# H2BR10.net
KiCad netlist of a schematic drawn in EAGLE
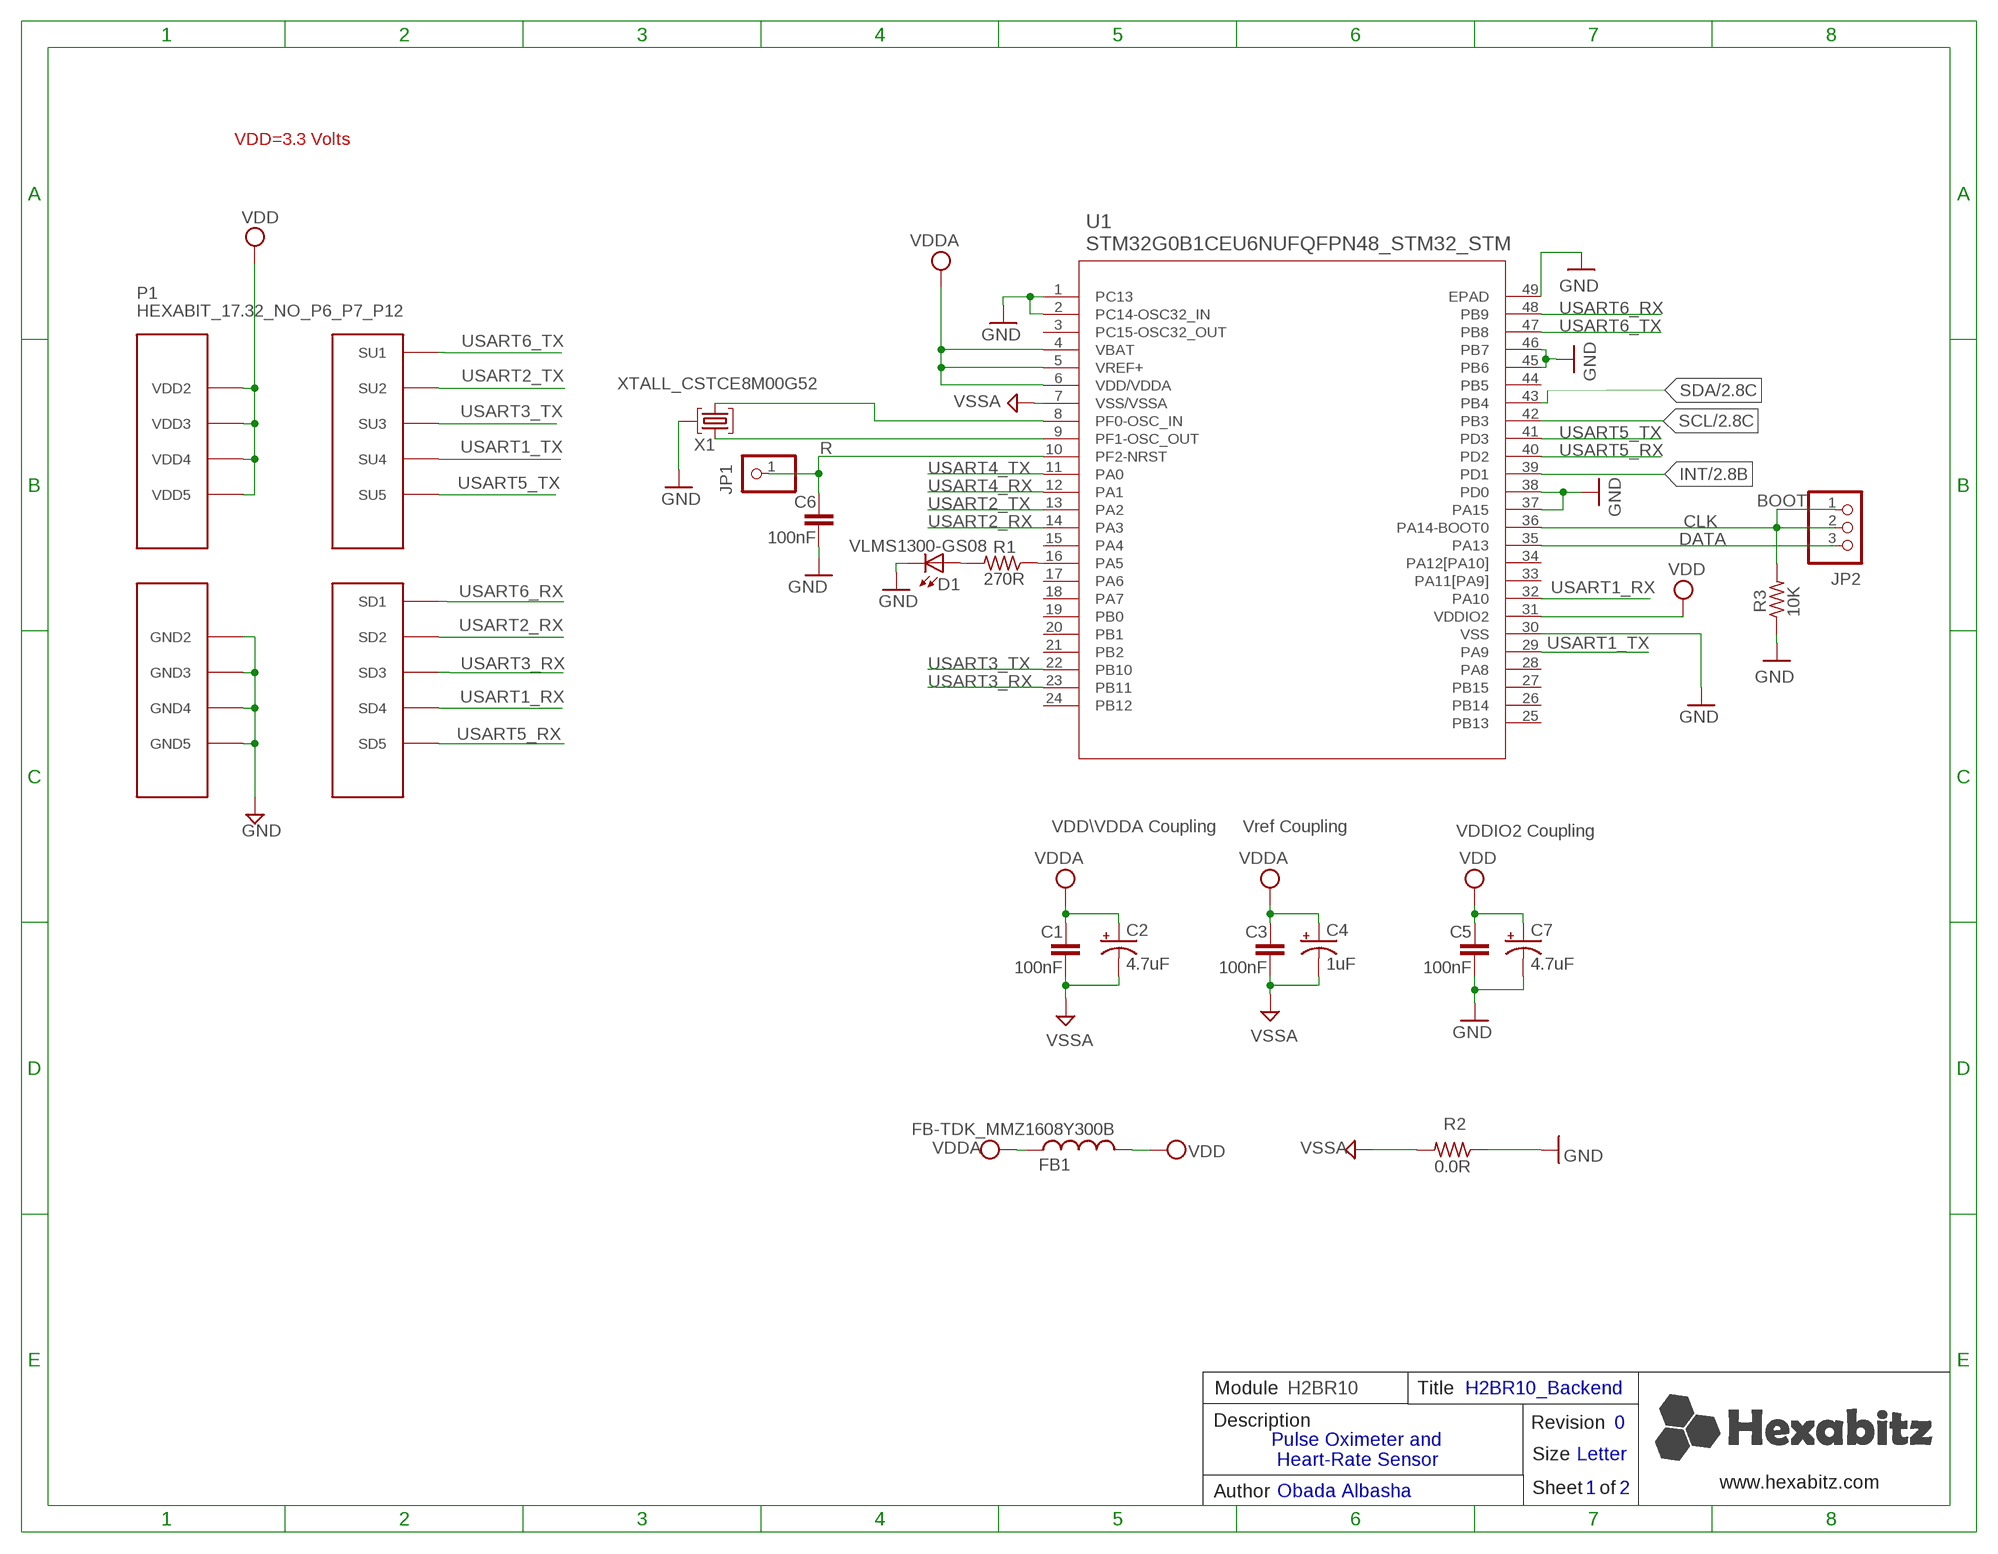
[diagram p0: schematic, sheet 1]
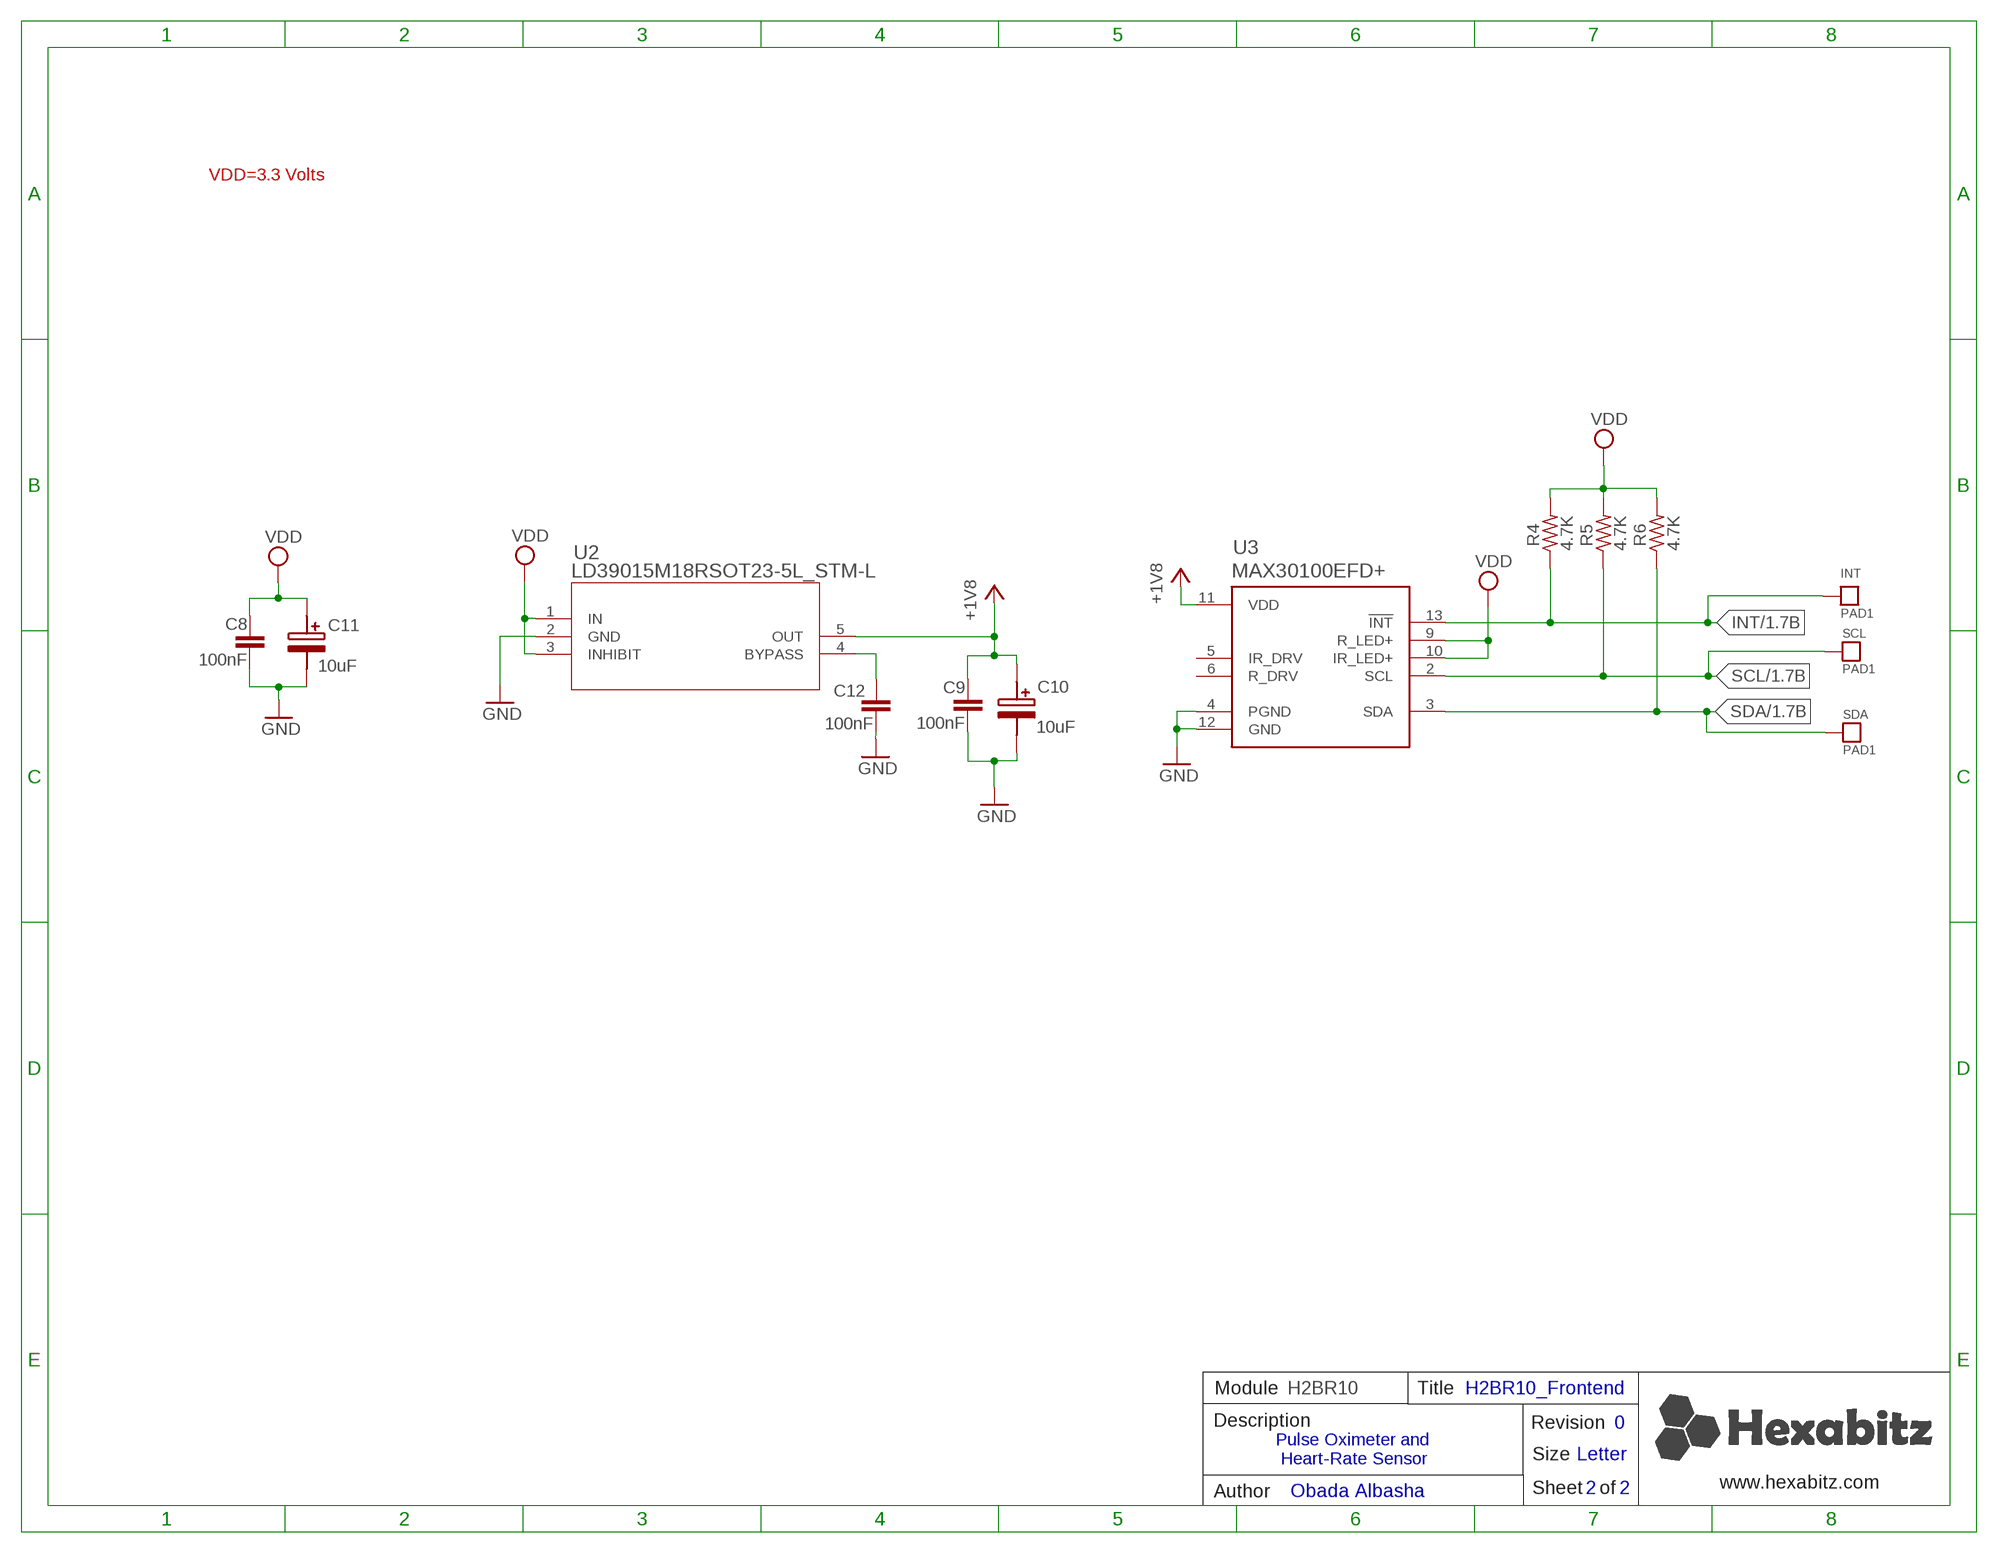
[diagram p1: schematic, sheet 2]

(export (version "E")
  (design (tool "Eeschema 10.0.6"))
  (components
    (comp (ref "C1")
      (value "100nF")
      (footprint "eagle-import:C-0603")
      (libsource (lib "eagle-import") (part "C-0603"))
    )
    (comp (ref "C2")
      (value "4.7uF")
      (footprint "eagle-import:C-0805-POL")
      (libsource (lib "eagle-import") (part "C-0805-POL"))
    )
    (comp (ref "C3")
      (value "100nF")
      (footprint "eagle-import:C-0603")
      (libsource (lib "eagle-import") (part "C-0603"))
    )
    (comp (ref "C4")
      (value "1uF")
      (footprint "eagle-import:C-0805-POL")
      (libsource (lib "eagle-import") (part "C-0805-POL"))
    )
    (comp (ref "C5")
      (value "100nF")
      (footprint "eagle-import:C-0603")
      (libsource (lib "eagle-import") (part "C-0603"))
    )
    (comp (ref "C6")
      (value "100nF")
      (footprint "eagle-import:C-0603")
      (libsource (lib "eagle-import") (part "C-0603"))
    )
    (comp (ref "C7")
      (value "4.7uF")
      (footprint "eagle-import:C-0805-POL")
      (libsource (lib "eagle-import") (part "C-0805-POL"))
    )
    (comp (ref "D1")
      (value "VLMS1300-GS08")
      (footprint "eagle-import:VLMS1300-GS08")
      (fields
        (field (name "MFN") "Vishay")
        (field (name "MPN") "VLMS1300-GS08")
        (field (name "OCTOPART_URL") "https://octopart.com/vlms1300-gs08-vishay-21709201?r=sp&s=_gcP4_q8T1SC6PJQPTQ9yA")
      )
      (libsource (lib "eagle-import") (part "VLMS1300-GS08"))
    )
    (comp (ref "FB1")
      (value "FB-TDK_MMZ1608Y300B")
      (footprint "eagle-import:FB-TDK_MMZ1608Y300B")
      (fields
        (field (name "MFN") "TDK ")
        (field (name "MPN") "MMZ1608Y300B")
        (field (name "OCTOPART_URL") "https://octopart.com/mmz1608y300b-tdk-368280?r=sp&s=cd9_2ZEqQ9q9UNBuQgHAiA")
      )
      (libsource (lib "eagle-import") (part "FB-TDK_MMZ1608Y300B"))
    )
    (comp (ref "JP1")
      (value "R")
      (footprint "eagle-import:1X01")
      (fields (field (name "MPN") "87227-1"))
      (libsource (lib "eagle-import") (part "PINHD-1X1"))
    )
    (comp (ref "JP2")
      (value "PINHD-1X3")
      (footprint "eagle-import:1X03")
      (libsource (lib "eagle-import") (part "PINHD-1X3"))
    )
    (comp (ref "P1")
      (value "HEXABIT_17.32_NO_P6_P7_P12")
      (footprint "eagle-import:HEXABIT_17.32_NO_P6_P7_P12")
      (libsource (lib "eagle-import") (part "HEXABIT_?_NO_P6_P7_P1217.32"))
    )
    (comp (ref "R1")
      (value "270R")
      (footprint "eagle-import:R-0603")
      (libsource (lib "eagle-import") (part "R-0603"))
    )
    (comp (ref "R2")
      (value "0.0R")
      (footprint "eagle-import:R-0603")
      (fields
        (field (name "MFN") "Yageo")
        (field (name "MPN") "RC0603JR-070RL")
        (field (name "OCTOPART_URL") "https://octopart.com/rc0603jr-070rl-yageo-1241539?r=sp&s=X2NteqRjRNWrnx42Y0aliA")
        (field (name "RESISTANCE") "0.0 Ohm")
      )
      (libsource (lib "eagle-import") (part "HEXABITZ_RCLS_33906182_R-0603"))
    )
    (comp (ref "R3")
      (value "10K")
      (footprint "eagle-import:R-0603")
      (libsource (lib "eagle-import") (part "R-0603"))
    )
    (comp (ref "U1")
      (value "STM32G0B1CEU6NUFQFPN48_STM32_STM")
      (footprint "eagle-import:UFQFPN48_STM32_STM")
      (fields
        (field (name "MPN") "STM32G0B1CEU6N")
        (field (name "COPYRIGHT") "Copyright (C) 2022 Ultra Librarian. All rights reserved.")
      )
      (libsource (lib "eagle-import") (part "STM32G0B1CEU6NUFQFPN48_STM32_STM"))
    )
    (comp (ref "X1")
      (value "XTALL_CSTCE8M00G52")
      (footprint "eagle-import:XTALL_CSTCE8M00G52")
      (fields (field (name "MPN") "CSTCE8M00G52Z-R0"))
      (libsource (lib "eagle-import") (part "XTALL_CSTCE8M00G52"))
    )
    (comp (ref "C8")
      (value "100nF")
      (footprint "eagle-import:C-0603")
      (libsource (lib "eagle-import") (part "C-0603"))
    )
    (comp (ref "C9")
      (value "100nF")
      (footprint "eagle-import:C-0603")
      (libsource (lib "eagle-import") (part "C-0603"))
    )
    (comp (ref "C10")
      (value "10uF")
      (footprint "eagle-import:T491A")
      (fields
        (field (name "MANUFACTURER_PART_NUMBER") "T491A106K010AT")
        (field (name "MOUSER_PART_NUMBER") "80-T491A106K010")
      )
      (libsource (lib "eagle-import") (part "T491A106K010AT"))
    )
    (comp (ref "C11")
      (value "10uF")
      (footprint "eagle-import:T491A")
      (fields
        (field (name "MANUFACTURER_PART_NUMBER") "T491A106K010AT")
        (field (name "MOUSER_PART_NUMBER") "80-T491A106K010")
      )
      (libsource (lib "eagle-import") (part "T491A106K010AT"))
    )
    (comp (ref "C12")
      (value "100nF")
      (footprint "eagle-import:C-0603")
      (libsource (lib "eagle-import") (part "C-0603"))
    )
    (comp (ref "INT")
      (value "PAD1")
      (footprint "eagle-import:PAD4")
      (libsource (lib "eagle-import") (part "PAD4"))
    )
    (comp (ref "R4")
      (value "4.7K")
      (footprint "eagle-import:R-0603")
      (libsource (lib "eagle-import") (part "R-0603"))
    )
    (comp (ref "R5")
      (value "4.7K")
      (footprint "eagle-import:R-0603")
      (libsource (lib "eagle-import") (part "R-0603"))
    )
    (comp (ref "R6")
      (value "4.7K")
      (footprint "eagle-import:R-0603")
      (libsource (lib "eagle-import") (part "R-0603"))
    )
    (comp (ref "SCL")
      (value "PAD1")
      (footprint "eagle-import:PAD4")
      (libsource (lib "eagle-import") (part "PAD4"))
    )
    (comp (ref "SDA")
      (value "PAD1")
      (footprint "eagle-import:PAD4")
      (libsource (lib "eagle-import") (part "PAD4"))
    )
    (comp (ref "U2")
      (value "LD39015M18RSOT23-5L_STM-L")
      (footprint "eagle-import:SOT23-5L_STM-L")
      (fields
        (field (name "MANUFACTURER_PART_NUMBER") "LD39015M18R")
        (field (name "COPYRIGHT") "Copyright (C) 2022 Ultra Librarian. All rights reserved.")
      )
      (libsource (lib "eagle-import") (part "LD39015M18RSOT23-5L_STM-L"))
    )
    (comp (ref "U3")
      (value "MAX30100EFD+")
      (footprint "eagle-import:LGA14R80P2X7_560X280X130")
      (fields (field (name "MF") "Maxim Integrated") (field (name "MP") "MAX30100EFD+T"))
      (libsource (lib "eagle-import") (part "MAX30100EFD+"))
    )
  )
  (nets
    (net (code "1") (name "+1V8") (class "Default")
      (node (ref "C10") (pin "1") (pinfunction "+_1") (pintype "bidirectional"))
      (node (ref "C9") (pin "1") (pinfunction "1_1") (pintype "passive"))
      (node (ref "U2") (pin "5") (pinfunction "OUT_5") (pintype "output"))
      (node (ref "U3") (pin "11") (pinfunction "VDD_11") (pintype "power_in"))
    )
    (net (code "2") (name "CLK") (class "Default")
      (node (ref "JP2") (pin "1") (pinfunction "1_1") (pintype "passive"))
      (node (ref "JP2") (pin "2") (pinfunction "2_2") (pintype "passive"))
      (node (ref "R3") (pin "2") (pinfunction "2_2") (pintype "passive"))
      (node (ref "U1") (pin "36") (pinfunction "PA14-BOOT0_36") (pintype "bidirectional"))
    )
    (net (code "3") (name "DATA") (class "Default")
      (node (ref "JP2") (pin "3") (pinfunction "3_3") (pintype "passive"))
      (node (ref "U1") (pin "35") (pinfunction "PA13_35") (pintype "bidirectional"))
    )
    (net (code "4") (name "GND") (class "Default")
      (node (ref "C10") (pin "2") (pinfunction "-_2") (pintype "bidirectional"))
      (node (ref "C11") (pin "2") (pinfunction "-_2") (pintype "bidirectional"))
      (node (ref "C12") (pin "2") (pinfunction "2_2") (pintype "passive"))
      (node (ref "C5") (pin "2") (pinfunction "2_2") (pintype "passive"))
      (node (ref "C6") (pin "2") (pinfunction "2_2") (pintype "passive"))
      (node (ref "C7") (pin "2") (pinfunction "-_2") (pintype "passive"))
      (node (ref "C8") (pin "2") (pinfunction "2_2") (pintype "passive"))
      (node (ref "C9") (pin "2") (pinfunction "2_2") (pintype "passive"))
      (node (ref "D1") (pin "C") (pinfunction "C_C") (pintype "passive"))
      (node (ref "P1") (pin "PAD_PD10") (pinfunction "GND4_PAD_PD10") (pintype "power_in"))
      (node (ref "P1") (pin "PAD_PD11") (pinfunction "GND5_PAD_PD11") (pintype "power_in"))
      (node (ref "P1") (pin "PAD_PD8") (pinfunction "GND2_PAD_PD8") (pintype "power_in"))
      (node (ref "P1") (pin "PAD_PD9") (pinfunction "GND3_PAD_PD9") (pintype "power_in"))
      (node (ref "R2") (pin "1") (pinfunction "1_1") (pintype "passive"))
      (node (ref "R3") (pin "1") (pinfunction "1_1") (pintype "passive"))
      (node (ref "U1") (pin "1") (pinfunction "PC13_1") (pintype "bidirectional"))
      (node (ref "U1") (pin "2") (pinfunction "PC14-OSC32_IN_2") (pintype "bidirectional"))
      (node (ref "U1") (pin "30") (pinfunction "VSS_30") (pintype "passive"))
      (node (ref "U1") (pin "37") (pinfunction "PA15_37") (pintype "bidirectional"))
      (node (ref "U1") (pin "38") (pinfunction "PD0_38") (pintype "bidirectional"))
      (node (ref "U1") (pin "45") (pinfunction "PB6_45") (pintype "bidirectional"))
      (node (ref "U1") (pin "46") (pinfunction "PB7_46") (pintype "bidirectional"))
      (node (ref "U1") (pin "49") (pinfunction "EPAD_49") (pintype "passive"))
      (node (ref "U2") (pin "2") (pinfunction "GND_2") (pintype "passive"))
      (node (ref "U3") (pin "12") (pinfunction "GND_12") (pintype "passive"))
      (node (ref "U3") (pin "4") (pinfunction "PGND_4") (pintype "passive"))
      (node (ref "X1") (pin "P$2") (pinfunction "2_P$2") (pintype "passive"))
    )
    (net (code "5") (name "INT") (class "Default")
      (node (ref "INT") (pin "P$1") (pinfunction "P$1_P$1") (pintype "passive"))
      (node (ref "R4") (pin "1") (pinfunction "1_1") (pintype "passive"))
      (node (ref "U1") (pin "39") (pinfunction "PD1_39") (pintype "bidirectional"))
      (node (ref "U3") (pin "13") (pinfunction "~{INT}_13") (pintype "input"))
    )
    (net (code "6") (name "Net-(D1-PadA)") (class "Default")
      (node (ref "D1") (pin "A") (pinfunction "A_A") (pintype "passive"))
      (node (ref "R1") (pin "2") (pinfunction "2_2") (pintype "passive"))
    )
    (net (code "7") (name "Net-(U1-PA5)") (class "Default")
      (node (ref "R1") (pin "1") (pinfunction "1_1") (pintype "passive"))
      (node (ref "U1") (pin "16") (pinfunction "PA5_16") (pintype "bidirectional"))
    )
    (net (code "8") (name "Net-(U1-PF0-OSC_IN)") (class "Default")
      (node (ref "U1") (pin "8") (pinfunction "PF0-OSC_IN_8") (pintype "bidirectional"))
      (node (ref "X1") (pin "P$3") (pinfunction "3_P$3") (pintype "passive"))
    )
    (net (code "9") (name "Net-(U1-PF1-OSC_OUT)") (class "Default")
      (node (ref "U1") (pin "9") (pinfunction "PF1-OSC_OUT_9") (pintype "bidirectional"))
      (node (ref "X1") (pin "P$1") (pinfunction "1_P$1") (pintype "passive"))
    )
    (net (code "10") (name "Net-(U1-PF2-NRST)") (class "Default")
      (node (ref "C6") (pin "1") (pinfunction "1_1") (pintype "passive"))
      (node (ref "JP1") (pin "1") (pinfunction "1_1") (pintype "passive"))
      (node (ref "U1") (pin "10") (pinfunction "PF2-NRST_10") (pintype "bidirectional"))
    )
    (net (code "11") (name "Net-(U2-BYPASS)") (class "Default")
      (node (ref "C12") (pin "1") (pinfunction "1_1") (pintype "passive"))
      (node (ref "U2") (pin "4") (pinfunction "BYPASS_4") (pintype "passive"))
    )
    (net (code "12") (name "SCL") (class "Default")
      (node (ref "R5") (pin "1") (pinfunction "1_1") (pintype "passive"))
      (node (ref "SCL") (pin "P$1") (pinfunction "P$1_P$1") (pintype "passive"))
      (node (ref "U1") (pin "42") (pinfunction "PB3_42") (pintype "bidirectional"))
      (node (ref "U3") (pin "2") (pinfunction "SCL_2") (pintype "input"))
    )
    (net (code "13") (name "SDA") (class "Default")
      (node (ref "R6") (pin "1") (pinfunction "1_1") (pintype "passive"))
      (node (ref "SDA") (pin "P$1") (pinfunction "P$1_P$1") (pintype "passive"))
      (node (ref "U1") (pin "43") (pinfunction "PB4_43") (pintype "bidirectional"))
      (node (ref "U3") (pin "3") (pinfunction "SDA_3") (pintype "bidirectional"))
    )
    (net (code "14") (name "USART1_RX") (class "Default")
      (node (ref "P1") (pin "PAD_PD4") (pinfunction "SD4_PAD_PD4") (pintype "bidirectional"))
      (node (ref "U1") (pin "32") (pinfunction "PA10_32") (pintype "bidirectional"))
    )
    (net (code "15") (name "USART1_TX") (class "Default")
      (node (ref "P1") (pin "PAD_PU4") (pinfunction "SU4_PAD_PU4") (pintype "bidirectional"))
      (node (ref "U1") (pin "29") (pinfunction "PA9_29") (pintype "bidirectional"))
    )
    (net (code "16") (name "USART2_RX") (class "Default")
      (node (ref "P1") (pin "PAD_PD2") (pinfunction "SD2_PAD_PD2") (pintype "bidirectional"))
      (node (ref "U1") (pin "14") (pinfunction "PA3_14") (pintype "bidirectional"))
    )
    (net (code "17") (name "USART2_TX") (class "Default")
      (node (ref "P1") (pin "PAD_PU2") (pinfunction "SU2_PAD_PU2") (pintype "bidirectional"))
      (node (ref "U1") (pin "13") (pinfunction "PA2_13") (pintype "bidirectional"))
    )
    (net (code "18") (name "USART3_RX") (class "Default")
      (node (ref "P1") (pin "PAD_PD3") (pinfunction "SD3_PAD_PD3") (pintype "bidirectional"))
      (node (ref "U1") (pin "23") (pinfunction "PB11_23") (pintype "bidirectional"))
    )
    (net (code "19") (name "USART3_TX") (class "Default")
      (node (ref "P1") (pin "PAD_PU3") (pinfunction "SU3_PAD_PU3") (pintype "bidirectional"))
      (node (ref "U1") (pin "22") (pinfunction "PB10_22") (pintype "bidirectional"))
    )
    (net (code "20") (name "USART4_RX") (class "Default")
      (node (ref "U1") (pin "12") (pinfunction "PA1_12") (pintype "bidirectional"))
    )
    (net (code "21") (name "USART4_TX") (class "Default")
      (node (ref "U1") (pin "11") (pinfunction "PA0_11") (pintype "bidirectional"))
    )
    (net (code "22") (name "USART5_RX") (class "Default")
      (node (ref "P1") (pin "PAD_PD5") (pinfunction "SD5_PAD_PD5") (pintype "bidirectional"))
      (node (ref "U1") (pin "40") (pinfunction "PD2_40") (pintype "bidirectional"))
    )
    (net (code "23") (name "USART5_TX") (class "Default")
      (node (ref "P1") (pin "PAD_PU5") (pinfunction "SU5_PAD_PU5") (pintype "bidirectional"))
      (node (ref "U1") (pin "41") (pinfunction "PD3_41") (pintype "bidirectional"))
    )
    (net (code "24") (name "USART6_RX") (class "Default")
      (node (ref "P1") (pin "PAD_PD1") (pinfunction "SD1_PAD_PD1") (pintype "bidirectional"))
      (node (ref "U1") (pin "48") (pinfunction "PB9_48") (pintype "bidirectional"))
    )
    (net (code "25") (name "USART6_TX") (class "Default")
      (node (ref "P1") (pin "PAD_PU1") (pinfunction "SU1_PAD_PU1") (pintype "bidirectional"))
      (node (ref "U1") (pin "47") (pinfunction "PB8_47") (pintype "bidirectional"))
    )
    (net (code "26") (name "VDD") (class "Default")
      (node (ref "C11") (pin "1") (pinfunction "+_1") (pintype "bidirectional"))
      (node (ref "C5") (pin "1") (pinfunction "1_1") (pintype "passive"))
      (node (ref "C7") (pin "1") (pinfunction "+_1") (pintype "passive"))
      (node (ref "C8") (pin "1") (pinfunction "1_1") (pintype "passive"))
      (node (ref "FB1") (pin "2") (pinfunction "2_2") (pintype "passive"))
      (node (ref "P1") (pin "PAD_PU10") (pinfunction "VDD4_PAD_PU10") (pintype "power_in"))
      (node (ref "P1") (pin "PAD_PU11") (pinfunction "VDD5_PAD_PU11") (pintype "power_in"))
      (node (ref "P1") (pin "PAD_PU8") (pinfunction "VDD2_PAD_PU8") (pintype "power_in"))
      (node (ref "P1") (pin "PAD_PU9") (pinfunction "VDD3_PAD_PU9") (pintype "power_in"))
      (node (ref "R4") (pin "2") (pinfunction "2_2") (pintype "passive"))
      (node (ref "R5") (pin "2") (pinfunction "2_2") (pintype "passive"))
      (node (ref "R6") (pin "2") (pinfunction "2_2") (pintype "passive"))
      (node (ref "U1") (pin "31") (pinfunction "VDDIO2_31") (pintype "power_in"))
      (node (ref "U2") (pin "1") (pinfunction "IN_1") (pintype "input"))
      (node (ref "U2") (pin "3") (pinfunction "INHIBIT_3") (pintype "bidirectional"))
      (node (ref "U3") (pin "10") (pinfunction "IR_LED+_10") (pintype "input"))
      (node (ref "U3") (pin "9") (pinfunction "R_LED+_9") (pintype "input"))
    )
    (net (code "27") (name "VDDA") (class "Default")
      (node (ref "C1") (pin "1") (pinfunction "1_1") (pintype "passive"))
      (node (ref "C2") (pin "1") (pinfunction "+_1") (pintype "passive"))
      (node (ref "C3") (pin "1") (pinfunction "1_1") (pintype "passive"))
      (node (ref "C4") (pin "1") (pinfunction "+_1") (pintype "passive"))
      (node (ref "FB1") (pin "1") (pinfunction "1_1") (pintype "passive"))
      (node (ref "U1") (pin "4") (pinfunction "VBAT_4") (pintype "power_in"))
      (node (ref "U1") (pin "5") (pinfunction "VREF+_5") (pintype "power_in"))
      (node (ref "U1") (pin "6") (pinfunction "VDD/VDDA_6") (pintype "power_in"))
    )
    (net (code "28") (name "VSSA") (class "Default")
      (node (ref "C1") (pin "2") (pinfunction "2_2") (pintype "passive"))
      (node (ref "C2") (pin "2") (pinfunction "-_2") (pintype "passive"))
      (node (ref "C3") (pin "2") (pinfunction "2_2") (pintype "passive"))
      (node (ref "C4") (pin "2") (pinfunction "-_2") (pintype "passive"))
      (node (ref "R2") (pin "2") (pinfunction "2_2") (pintype "passive"))
      (node (ref "U1") (pin "7") (pinfunction "VSS/VSSA_7") (pintype "passive"))
    )
    (net (code "29") (name "unconnected-(U1-PA4-Pad15)") (class "Default")
      (node (ref "U1") (pin "15") (pinfunction "PA4_15") (pintype "bidirectional"))
    )
    (net (code "30") (name "unconnected-(U1-PA6-Pad17)") (class "Default")
      (node (ref "U1") (pin "17") (pinfunction "PA6_17") (pintype "bidirectional"))
    )
    (net (code "31") (name "unconnected-(U1-PA7-Pad18)") (class "Default")
      (node (ref "U1") (pin "18") (pinfunction "PA7_18") (pintype "bidirectional"))
    )
    (net (code "32") (name "unconnected-(U1-PA8-Pad28)") (class "Default")
      (node (ref "U1") (pin "28") (pinfunction "PA8_28") (pintype "bidirectional"))
    )
    (net (code "33") (name "unconnected-(U1-PA11[PA9]-Pad33)") (class "Default")
      (node (ref "U1") (pin "33") (pinfunction "PA11[PA9]_33") (pintype "bidirectional"))
    )
    (net (code "34") (name "unconnected-(U1-PA12[PA10]-Pad34)") (class "Default")
      (node (ref "U1") (pin "34") (pinfunction "PA12[PA10]_34") (pintype "bidirectional"))
    )
    (net (code "35") (name "unconnected-(U1-PB0-Pad19)") (class "Default")
      (node (ref "U1") (pin "19") (pinfunction "PB0_19") (pintype "bidirectional"))
    )
    (net (code "36") (name "unconnected-(U1-PB1-Pad20)") (class "Default")
      (node (ref "U1") (pin "20") (pinfunction "PB1_20") (pintype "bidirectional"))
    )
    (net (code "37") (name "unconnected-(U1-PB2-Pad21)") (class "Default")
      (node (ref "U1") (pin "21") (pinfunction "PB2_21") (pintype "bidirectional"))
    )
    (net (code "38") (name "unconnected-(U1-PB5-Pad44)") (class "Default")
      (node (ref "U1") (pin "44") (pinfunction "PB5_44") (pintype "bidirectional"))
    )
    (net (code "39") (name "unconnected-(U1-PB12-Pad24)") (class "Default")
      (node (ref "U1") (pin "24") (pinfunction "PB12_24") (pintype "bidirectional"))
    )
    (net (code "40") (name "unconnected-(U1-PB13-Pad25)") (class "Default")
      (node (ref "U1") (pin "25") (pinfunction "PB13_25") (pintype "bidirectional"))
    )
    (net (code "41") (name "unconnected-(U1-PB14-Pad26)") (class "Default")
      (node (ref "U1") (pin "26") (pinfunction "PB14_26") (pintype "bidirectional"))
    )
    (net (code "42") (name "unconnected-(U1-PB15-Pad27)") (class "Default")
      (node (ref "U1") (pin "27") (pinfunction "PB15_27") (pintype "bidirectional"))
    )
    (net (code "43") (name "unconnected-(U1-PC15-OSC32_OUT-Pad3)") (class "Default")
      (node (ref "U1") (pin "3") (pinfunction "PC15-OSC32_OUT_3") (pintype "bidirectional"))
    )
    (net (code "44") (name "unconnected-(U3-IR_DRV-Pad5)") (class "Default")
      (node (ref "U3") (pin "5") (pinfunction "IR_DRV_5") (pintype "passive"))
    )
    (net (code "45") (name "unconnected-(U3-R_DRV-Pad6)") (class "Default")
      (node (ref "U3") (pin "6") (pinfunction "R_DRV_6") (pintype "passive"))
    )
  )
)
